# WCHA_SCH.net
KiCad netlist of a schematic drawn in Altium Designer
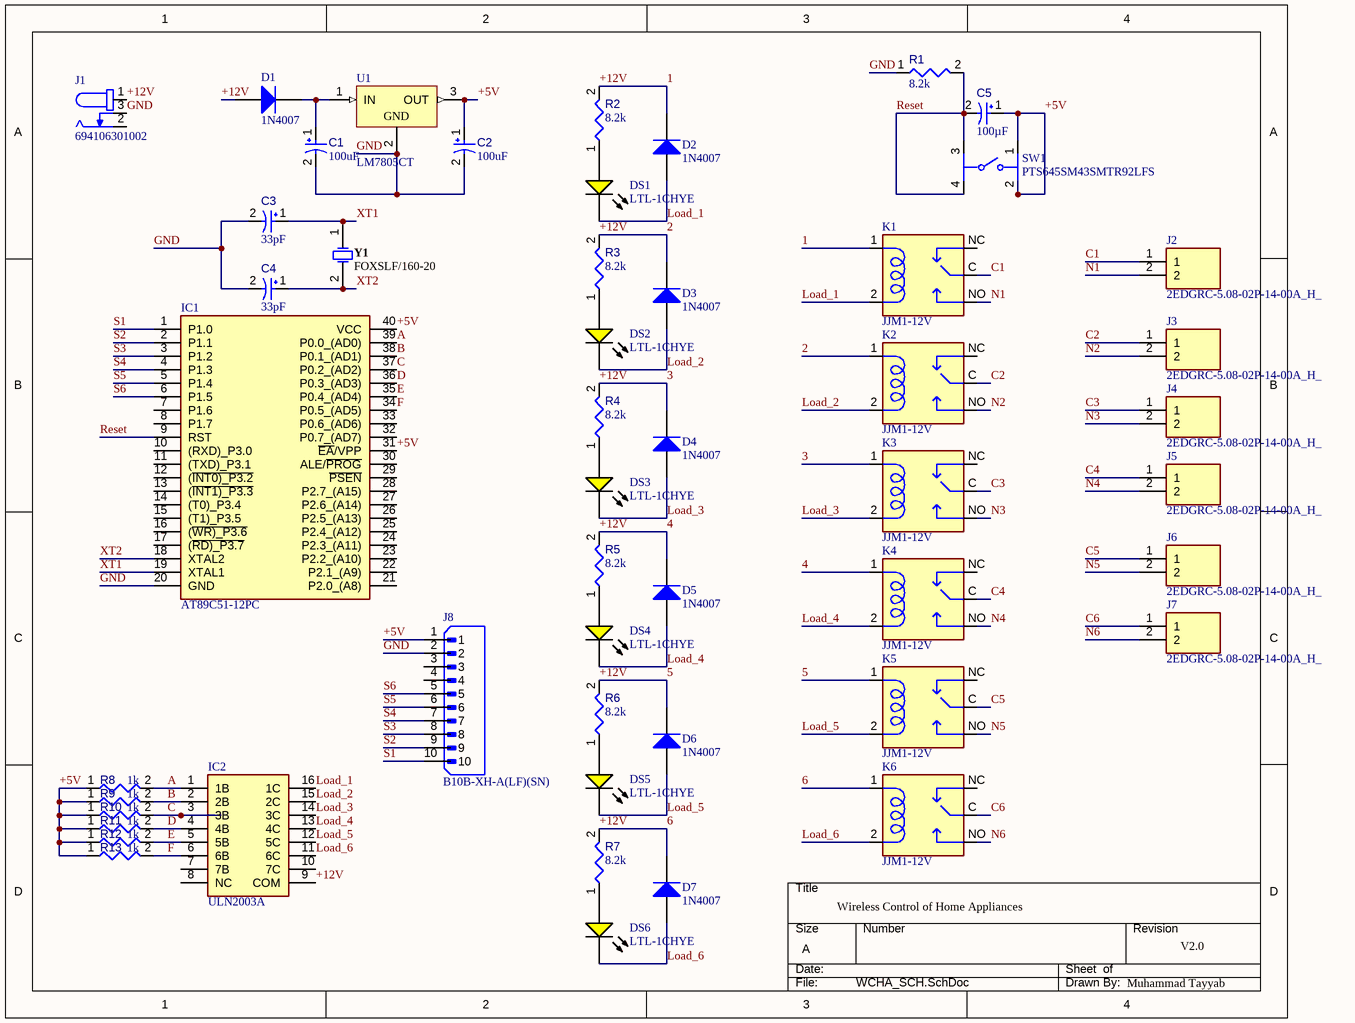
[diagram p0: WCHA_SCH.SchDoc]

(export (version "E")
  (design (tool "Eeschema 10.0.6"))
  (components
    (comp (ref "C1")
      (value "100uF")
      (footprint "CAPPR65-500-2000X1000X2200")
      (description "Aluminum Electrolytic Capacitor, 1000 uF, +/- 20%, 25 V, -40 to 85 degC, 2-Pin THD, RoHS, Bulk")
      (fields (field (name "TOLERANCE") "20%") (field (name "MANUFACTURER") "Panasonic"))
      (libsource (lib "Muhammad Tayyab") (part "CAP-P-2"))
    )
    (comp (ref "C2")
      (value "100uF")
      (footprint "CAPPR65-500-2000X1000X2200")
      (description "Aluminum Electrolytic Capacitor, 1000 uF, +/- 20%, 25 V, -40 to 85 degC, 2-Pin THD, RoHS, Bulk")
      (fields (field (name "TOLERANCE") "20%") (field (name "MANUFACTURER") "Panasonic"))
      (libsource (lib "Muhammad Tayyab") (part "CAP-P-2"))
    )
    (comp (ref "C3")
      (value "33pF")
      (footprint "CAPPR65-350-1150X800X1250")
      (description "Aluminum Electrolytic Capacitor, 100 uF, +/- 20%, 50 V, -40 to 85 degC, 2-Pin THD, RoHS, Bulk")
      (fields (field (name "MANUFACTURER") "Panasonic") (field (name "TOLERANCE") "20%"))
      (libsource (lib "") (part "CAP-P-2_1"))
    )
    (comp (ref "C4")
      (value "33pF")
      (footprint "CAPPR65-350-1150X800X1250")
      (description "Aluminum Electrolytic Capacitor, 100 uF, +/- 20%, 50 V, -40 to 85 degC, 2-Pin THD, RoHS, Bulk")
      (fields (field (name "MANUFACTURER") "Panasonic") (field (name "TOLERANCE") "20%"))
      (libsource (lib "") (part "CAP-P-2_1"))
    )
    (comp (ref "C5")
      (value "100µF")
      (footprint "CAPPR65-350-1150X800X1250")
      (description "Aluminum Electrolytic Capacitor, 100 uF, +/- 20%, 50 V, -40 to 85 degC, 2-Pin THD, RoHS, Bulk")
      (fields (field (name "MANUFACTURER") "Panasonic") (field (name "TOLERANCE") "20%"))
      (libsource (lib "") (part "CAP-P-2_1"))
    )
    (comp (ref "D1")
      (value "1N4007")
      (footprint "FAIR-DO-41-2")
      (description "General Purpose Rectifier, 1.1 V, 1.0 A, -55 to 175 degC, 2-Pin DO-41, RoHS, Tape and Reel")
      (fields (field (name "MANUFACTURER") "Fairchild"))
      (libsource (lib "Muhammad Tayyab") (part "KESE-D_K1A2-2"))
    )
    (comp (ref "D2")
      (value "1N4007")
      (footprint "FAIR-DO-41-2")
      (description "General Purpose Rectifier, 1.1 V, 1.0 A, -55 to 175 degC, 2-Pin DO-41, RoHS, Tape and Reel")
      (fields (field (name "MANUFACTURER") "Fairchild"))
      (libsource (lib "Muhammad Tayyab") (part "KESE-D_K1A2-2"))
    )
    (comp (ref "D3")
      (value "1N4007")
      (footprint "FAIR-DO-41-2")
      (description "General Purpose Rectifier, 1.1 V, 1.0 A, -55 to 175 degC, 2-Pin DO-41, RoHS, Tape and Reel")
      (fields (field (name "MANUFACTURER") "Fairchild"))
      (libsource (lib "Muhammad Tayyab") (part "KESE-D_K1A2-2"))
    )
    (comp (ref "D4")
      (value "1N4007")
      (footprint "FAIR-DO-41-2")
      (description "General Purpose Rectifier, 1.1 V, 1.0 A, -55 to 175 degC, 2-Pin DO-41, RoHS, Tape and Reel")
      (fields (field (name "MANUFACTURER") "Fairchild"))
      (libsource (lib "Muhammad Tayyab") (part "KESE-D_K1A2-2"))
    )
    (comp (ref "D5")
      (value "1N4007")
      (footprint "FAIR-DO-41-2")
      (description "General Purpose Rectifier, 1.1 V, 1.0 A, -55 to 175 degC, 2-Pin DO-41, RoHS, Tape and Reel")
      (fields (field (name "MANUFACTURER") "Fairchild"))
      (libsource (lib "Muhammad Tayyab") (part "KESE-D_K1A2-2"))
    )
    (comp (ref "D6")
      (value "1N4007")
      (footprint "FAIR-DO-41-2")
      (description "General Purpose Rectifier, 1.1 V, 1.0 A, -55 to 175 degC, 2-Pin DO-41, RoHS, Tape and Reel")
      (fields (field (name "MANUFACTURER") "Fairchild"))
      (libsource (lib "Muhammad Tayyab") (part "KESE-D_K1A2-2"))
    )
    (comp (ref "D7")
      (value "1N4007")
      (footprint "FAIR-DO-41-2")
      (description "General Purpose Rectifier, 1.1 V, 1.0 A, -55 to 175 degC, 2-Pin DO-41, RoHS, Tape and Reel")
      (fields (field (name "MANUFACTURER") "Fairchild"))
      (libsource (lib "Muhammad Tayyab") (part "KESE-D_K1A2-2"))
    )
    (comp (ref "DS1")
      (value "LTL-1CHYE")
      (footprint "LTST-LTL-1CHYE")
      (description "LED Uni-Color Yellow, 60 mW, 20 mA, -55 to 100 degC, 2-Pin THD, RoHS, Bulk")
      (fields (field (name "MANUFACTURER") "Lite-On"))
      (libsource (lib "Muhammad Tayyab") (part "LED-YELLOW-AK-2"))
    )
    (comp (ref "DS2")
      (value "LTL-1CHYE")
      (footprint "LTST-LTL-1CHYE")
      (description "LED Uni-Color Yellow, 60 mW, 20 mA, -55 to 100 degC, 2-Pin THD, RoHS, Bulk")
      (fields (field (name "MANUFACTURER") "Lite-On"))
      (libsource (lib "Muhammad Tayyab") (part "LED-YELLOW-AK-2"))
    )
    (comp (ref "DS3")
      (value "LTL-1CHYE")
      (footprint "LTST-LTL-1CHYE")
      (description "LED Uni-Color Yellow, 60 mW, 20 mA, -55 to 100 degC, 2-Pin THD, RoHS, Bulk")
      (fields (field (name "MANUFACTURER") "Lite-On"))
      (libsource (lib "Muhammad Tayyab") (part "LED-YELLOW-AK-2"))
    )
    (comp (ref "DS4")
      (value "LTL-1CHYE")
      (footprint "LTST-LTL-1CHYE")
      (description "LED Uni-Color Yellow, 60 mW, 20 mA, -55 to 100 degC, 2-Pin THD, RoHS, Bulk")
      (fields (field (name "MANUFACTURER") "Lite-On"))
      (libsource (lib "Muhammad Tayyab") (part "LED-YELLOW-AK-2"))
    )
    (comp (ref "DS5")
      (value "LTL-1CHYE")
      (footprint "LTST-LTL-1CHYE")
      (description "LED Uni-Color Yellow, 60 mW, 20 mA, -55 to 100 degC, 2-Pin THD, RoHS, Bulk")
      (fields (field (name "MANUFACTURER") "Lite-On"))
      (libsource (lib "Muhammad Tayyab") (part "LED-YELLOW-AK-2"))
    )
    (comp (ref "DS6")
      (value "LTL-1CHYE")
      (footprint "LTST-LTL-1CHYE")
      (description "LED Uni-Color Yellow, 60 mW, 20 mA, -55 to 100 degC, 2-Pin THD, RoHS, Bulk")
      (fields (field (name "MANUFACTURER") "Lite-On"))
      (libsource (lib "Muhammad Tayyab") (part "LED-YELLOW-AK-2"))
    )
    (comp (ref "IC1")
      (value "AT89C51-12PC")
      (footprint "SamacSys:DIP1525W56P254L5220H559Q40N")
      (description "Integrated Circuit")
      (fields (field (name "MOUSER PART NUMBER") "556-AT89C51-12PC"))
      (libsource (lib "*") (part "AT89C51-12PC"))
    )
    (comp (ref "IC2")
      (value "ULN2003A")
      (footprint "SamacSys:DIP762W54P254L1918H445Q16N")
      (description "Integrated Circuit")
      (libsource (lib "*") (part "ULN2003A"))
    )
    (comp (ref "J1")
      (value "694106301002")
      (footprint "694106301002:694106301002")
      (fields (field (name "MF") "{'manufacturer': u'Wurth Elektronik'}"))
      (libsource (lib "*") (part "694106301002"))
    )
    (comp (ref "J2")
      (value "2EDGRC-5.08-02P-14-00A_H_")
      (footprint "SHDRRA2W100P0X508_1X2_1156X1210X780P")
      (description "R/A SHrouded Header")
      (fields (field (name "MANUFACTURER_PART_NUMBER") "2EDGRC-5.08-02P-14-00A(H)"))
      (libsource (lib "Muhammad Tayyab") (part "2EDGRC-5.08-02P-14-00A_H_"))
    )
    (comp (ref "J3")
      (value "2EDGRC-5.08-02P-14-00A_H_")
      (footprint "SHDRRA2W100P0X508_1X2_1156X1210X780P")
      (description "R/A SHrouded Header")
      (fields (field (name "MANUFACTURER_PART_NUMBER") "2EDGRC-5.08-02P-14-00A(H)"))
      (libsource (lib "Muhammad Tayyab") (part "2EDGRC-5.08-02P-14-00A_H_"))
    )
    (comp (ref "J4")
      (value "2EDGRC-5.08-02P-14-00A_H_")
      (footprint "SHDRRA2W100P0X508_1X2_1156X1210X780P")
      (description "R/A SHrouded Header")
      (fields (field (name "MANUFACTURER_PART_NUMBER") "2EDGRC-5.08-02P-14-00A(H)"))
      (libsource (lib "Muhammad Tayyab") (part "2EDGRC-5.08-02P-14-00A_H_"))
    )
    (comp (ref "J5")
      (value "2EDGRC-5.08-02P-14-00A_H_")
      (footprint "SHDRRA2W100P0X508_1X2_1156X1210X780P")
      (description "R/A SHrouded Header")
      (fields (field (name "MANUFACTURER_PART_NUMBER") "2EDGRC-5.08-02P-14-00A(H)"))
      (libsource (lib "Muhammad Tayyab") (part "2EDGRC-5.08-02P-14-00A_H_"))
    )
    (comp (ref "J6")
      (value "2EDGRC-5.08-02P-14-00A_H_")
      (footprint "SHDRRA2W100P0X508_1X2_1156X1210X780P")
      (description "R/A SHrouded Header")
      (fields (field (name "MANUFACTURER_PART_NUMBER") "2EDGRC-5.08-02P-14-00A(H)"))
      (libsource (lib "Muhammad Tayyab") (part "2EDGRC-5.08-02P-14-00A_H_"))
    )
    (comp (ref "J7")
      (value "2EDGRC-5.08-02P-14-00A_H_")
      (footprint "SHDRRA2W100P0X508_1X2_1156X1210X780P")
      (description "R/A SHrouded Header")
      (fields (field (name "MANUFACTURER_PART_NUMBER") "2EDGRC-5.08-02P-14-00A(H)"))
      (libsource (lib "Muhammad Tayyab") (part "2EDGRC-5.08-02P-14-00A_H_"))
    )
    (comp (ref "J8")
      (value "B10B-XH-A(LF)(SN)")
      (footprint "B10B-XH-A(LF)(SN):JST_B10B-XH-A(LF)(SN)")
      (fields (field (name "MF") "{'manufacturer': u'JST Sales'}"))
      (libsource (lib "*") (part "B10B-XH-A(LF)(SN)"))
    )
    (comp (ref "K1")
      (value "JJM1-12V")
      (footprint "JJM1-12V:RELAY_JJM1-12V")
      (fields (field (name "MF") "{'manufacturer': u'Panasonic Electric'}"))
      (libsource (lib "*") (part "JJM1-12V"))
    )
    (comp (ref "K2")
      (value "JJM1-12V")
      (footprint "JJM1-12V:RELAY_JJM1-12V")
      (fields (field (name "MF") "{'manufacturer': u'Panasonic Electric'}"))
      (libsource (lib "*") (part "JJM1-12V"))
    )
    (comp (ref "K3")
      (value "JJM1-12V")
      (footprint "JJM1-12V:RELAY_JJM1-12V")
      (fields (field (name "MF") "{'manufacturer': u'Panasonic Electric'}"))
      (libsource (lib "*") (part "JJM1-12V"))
    )
    (comp (ref "K4")
      (value "JJM1-12V")
      (footprint "JJM1-12V:RELAY_JJM1-12V")
      (fields (field (name "MF") "{'manufacturer': u'Panasonic Electric'}"))
      (libsource (lib "*") (part "JJM1-12V"))
    )
    (comp (ref "K5")
      (value "JJM1-12V")
      (footprint "JJM1-12V:RELAY_JJM1-12V")
      (fields (field (name "MF") "{'manufacturer': u'Panasonic Electric'}"))
      (libsource (lib "*") (part "JJM1-12V"))
    )
    (comp (ref "K6")
      (value "JJM1-12V")
      (footprint "JJM1-12V:RELAY_JJM1-12V")
      (fields (field (name "MF") "{'manufacturer': u'Panasonic Electric'}"))
      (libsource (lib "*") (part "JJM1-12V"))
    )
    (comp (ref "R1")
      (value "8.2k")
      (footprint "RESA60-630X240")
      (description "Axial Resistor, 47.5 KOhm, +/- 1%, 0.25 W, -55 to 155 degC, 2-Pin THD, RoHS, Bulk")
      (fields (field (name "MANUFACTURER") "Yageo") (field (name "TOLERANCE") "1%"))
      (libsource (lib "Muhammad Tayyab") (part "RES-2"))
    )
    (comp (ref "R2")
      (value "8.2k")
      (footprint "RESA60-630X240")
      (description "Axial Resistor, 47.5 KOhm, +/- 1%, 0.25 W, -55 to 155 degC, 2-Pin THD, RoHS, Bulk")
      (fields (field (name "MANUFACTURER") "Yageo") (field (name "TOLERANCE") "1%"))
      (libsource (lib "Muhammad Tayyab") (part "RES-2"))
    )
    (comp (ref "R3")
      (value "8.2k")
      (footprint "RESA60-630X240")
      (description "Axial Resistor, 47.5 KOhm, +/- 1%, 0.25 W, -55 to 155 degC, 2-Pin THD, RoHS, Bulk")
      (fields (field (name "MANUFACTURER") "Yageo") (field (name "TOLERANCE") "1%"))
      (libsource (lib "Muhammad Tayyab") (part "RES-2"))
    )
    (comp (ref "R4")
      (value "8.2k")
      (footprint "RESA60-630X240")
      (description "Axial Resistor, 47.5 KOhm, +/- 1%, 0.25 W, -55 to 155 degC, 2-Pin THD, RoHS, Bulk")
      (fields (field (name "MANUFACTURER") "Yageo") (field (name "TOLERANCE") "1%"))
      (libsource (lib "Muhammad Tayyab") (part "RES-2"))
    )
    (comp (ref "R5")
      (value "8.2k")
      (footprint "RESA60-630X240")
      (description "Axial Resistor, 47.5 KOhm, +/- 1%, 0.25 W, -55 to 155 degC, 2-Pin THD, RoHS, Bulk")
      (fields (field (name "MANUFACTURER") "Yageo") (field (name "TOLERANCE") "1%"))
      (libsource (lib "Muhammad Tayyab") (part "RES-2"))
    )
    (comp (ref "R6")
      (value "8.2k")
      (footprint "RESA60-630X240")
      (description "Axial Resistor, 47.5 KOhm, +/- 1%, 0.25 W, -55 to 155 degC, 2-Pin THD, RoHS, Bulk")
      (fields (field (name "MANUFACTURER") "Yageo") (field (name "TOLERANCE") "1%"))
      (libsource (lib "Muhammad Tayyab") (part "RES-2"))
    )
    (comp (ref "R7")
      (value "8.2k")
      (footprint "RESA60-630X240")
      (description "Axial Resistor, 47.5 KOhm, +/- 1%, 0.25 W, -55 to 155 degC, 2-Pin THD, RoHS, Bulk")
      (fields (field (name "MANUFACTURER") "Yageo") (field (name "TOLERANCE") "1%"))
      (libsource (lib "Muhammad Tayyab") (part "RES-2"))
    )
    (comp (ref "R8")
      (value "1k")
      (footprint "RESA60-630X240")
      (description "Axial Resistor, 47.5 KOhm, +/- 1%, 0.25 W, -55 to 155 degC, 2-Pin THD, RoHS, Bulk")
      (fields (field (name "MANUFACTURER") "Yageo") (field (name "TOLERANCE") "1%"))
      (libsource (lib "Muhammad Tayyab") (part "RES-2"))
    )
    (comp (ref "R9")
      (value "1k")
      (footprint "RESA60-630X240")
      (description "Axial Resistor, 47.5 KOhm, +/- 1%, 0.25 W, -55 to 155 degC, 2-Pin THD, RoHS, Bulk")
      (fields (field (name "MANUFACTURER") "Yageo") (field (name "TOLERANCE") "1%"))
      (libsource (lib "Muhammad Tayyab") (part "RES-2"))
    )
    (comp (ref "R10")
      (value "1k")
      (footprint "RESA60-630X240")
      (description "Axial Resistor, 47.5 KOhm, +/- 1%, 0.25 W, -55 to 155 degC, 2-Pin THD, RoHS, Bulk")
      (fields (field (name "MANUFACTURER") "Yageo") (field (name "TOLERANCE") "1%"))
      (libsource (lib "Muhammad Tayyab") (part "RES-2"))
    )
    (comp (ref "R11")
      (value "1k")
      (footprint "RESA60-630X240")
      (description "Axial Resistor, 47.5 KOhm, +/- 1%, 0.25 W, -55 to 155 degC, 2-Pin THD, RoHS, Bulk")
      (fields (field (name "MANUFACTURER") "Yageo") (field (name "TOLERANCE") "1%"))
      (libsource (lib "Muhammad Tayyab") (part "RES-2"))
    )
    (comp (ref "R12")
      (value "1k")
      (footprint "RESA60-630X240")
      (description "Axial Resistor, 47.5 KOhm, +/- 1%, 0.25 W, -55 to 155 degC, 2-Pin THD, RoHS, Bulk")
      (fields (field (name "MANUFACTURER") "Yageo") (field (name "TOLERANCE") "1%"))
      (libsource (lib "Muhammad Tayyab") (part "RES-2"))
    )
    (comp (ref "R13")
      (value "1k")
      (footprint "RESA60-630X240")
      (description "Axial Resistor, 47.5 KOhm, +/- 1%, 0.25 W, -55 to 155 degC, 2-Pin THD, RoHS, Bulk")
      (fields (field (name "MANUFACTURER") "Yageo") (field (name "TOLERANCE") "1%"))
      (libsource (lib "Muhammad Tayyab") (part "RES-2"))
    )
    (comp (ref "SW1")
      (value "PTS645SM43SMTR92LFS")
      (footprint "FP-PTS645SM43SMTR92LFS-MFG")
      (description "SWITCH TACTILE SPST-NO 0.05A 12V")
      (libsource (lib "Altium Content Vault") (part "1adf0dd01260c80cf25a44bfd6b99ba"))
    )
    (comp (ref "U1")
      (value "LM7805CT")
      (footprint "FAIR-TO-220-3")
      (description "Positive Voltage Regulator, 5 V, 1 A, -40 to 125 degC, 3-Pin TO-220, RoHS, Tube")
      (fields (field (name "MANUFACTURER") "FairchildSemiconductor"))
      (libsource (lib "Altium Content Vault") (part "FAIR-LM7805CT-TO220-3"))
    )
    (comp (ref "Y1")
      (value "FOXSLF/160-20")
      (footprint "FOX-FOXSLF160-20")
      (fields (field (name "MANUFACTURER") "FOX Electronics") (field (name "TOLERANCE") "50ppm"))
      (libsource (lib "Muhammad Tayyab") (part "XTAL-1-2-2"))
    )
  )
  (nets
    (net (code "1") (name "/+5V") (class "Default")
      (node (ref "C2") (pin "1") (pinfunction "1_1") (pintype "passive"))
      (node (ref "C5") (pin "1") (pinfunction "1_1") (pintype "passive"))
      (node (ref "IC1") (pin "31") (pinfunction "~{EA}/VPP_31") (pintype "passive"))
      (node (ref "IC1") (pin "40") (pinfunction "VCC_40") (pintype "passive"))
      (node (ref "J8") (pin "1") (pinfunction "1_1") (pintype "passive"))
      (node (ref "R10") (pin "1") (pinfunction "1_1") (pintype "passive"))
      (node (ref "R11") (pin "1") (pinfunction "1_1") (pintype "passive"))
      (node (ref "R12") (pin "1") (pinfunction "1_1") (pintype "passive"))
      (node (ref "R13") (pin "1") (pinfunction "1_1") (pintype "passive"))
      (node (ref "R8") (pin "1") (pinfunction "1_1") (pintype "passive"))
      (node (ref "R9") (pin "1") (pinfunction "1_1") (pintype "passive"))
      (node (ref "SW1") (pin "1") (pinfunction "1_1") (pintype "passive"))
      (node (ref "SW1") (pin "2") (pinfunction "2_2") (pintype "passive"))
      (node (ref "U1") (pin "3") (pinfunction "OUT_3") (pintype "output"))
    )
    (net (code "2") (name "/+12V") (class "Default")
      (node (ref "D1") (pin "2") (pinfunction "A_2") (pintype "passive"))
      (node (ref "D2") (pin "1") (pinfunction "K_1") (pintype "passive"))
      (node (ref "D3") (pin "1") (pinfunction "K_1") (pintype "passive"))
      (node (ref "D4") (pin "1") (pinfunction "K_1") (pintype "passive"))
      (node (ref "D5") (pin "1") (pinfunction "K_1") (pintype "passive"))
      (node (ref "D6") (pin "1") (pinfunction "K_1") (pintype "passive"))
      (node (ref "D7") (pin "1") (pinfunction "K_1") (pintype "passive"))
      (node (ref "IC2") (pin "9") (pinfunction "COM_9") (pintype "passive"))
      (node (ref "J1") (pin "1") (pinfunction "1_1") (pintype "passive"))
      (node (ref "K1") (pin "1") (pinfunction "C1_1") (pintype "passive"))
      (node (ref "K2") (pin "1") (pinfunction "C1_1") (pintype "passive"))
      (node (ref "K3") (pin "1") (pinfunction "C1_1") (pintype "passive"))
      (node (ref "K4") (pin "1") (pinfunction "C1_1") (pintype "passive"))
      (node (ref "K5") (pin "1") (pinfunction "C1_1") (pintype "passive"))
      (node (ref "K6") (pin "1") (pinfunction "C1_1") (pintype "passive"))
      (node (ref "R2") (pin "2") (pinfunction "2_2") (pintype "passive"))
      (node (ref "R3") (pin "2") (pinfunction "2_2") (pintype "passive"))
      (node (ref "R4") (pin "2") (pinfunction "2_2") (pintype "passive"))
      (node (ref "R5") (pin "2") (pinfunction "2_2") (pintype "passive"))
      (node (ref "R6") (pin "2") (pinfunction "2_2") (pintype "passive"))
      (node (ref "R7") (pin "2") (pinfunction "2_2") (pintype "passive"))
    )
    (net (code "4") (name "/A") (class "Default")
      (node (ref "IC1") (pin "39") (pinfunction "P0.0_(AD0)_39") (pintype "passive"))
      (node (ref "IC2") (pin "1") (pinfunction "1B_1") (pintype "passive"))
      (node (ref "R8") (pin "2") (pinfunction "2_2") (pintype "passive"))
    )
    (net (code "5") (name "/B") (class "Default")
      (node (ref "IC1") (pin "38") (pinfunction "P0.1_(AD1)_38") (pintype "passive"))
      (node (ref "IC2") (pin "2") (pinfunction "2B_2") (pintype "passive"))
      (node (ref "R9") (pin "2") (pinfunction "2_2") (pintype "passive"))
    )
    (net (code "6") (name "/C") (class "Default")
      (node (ref "IC1") (pin "37") (pinfunction "P0.2_(AD2)_37") (pintype "passive"))
      (node (ref "IC2") (pin "3") (pinfunction "3B_3") (pintype "passive"))
      (node (ref "R10") (pin "2") (pinfunction "2_2") (pintype "passive"))
    )
    (net (code "7") (name "/C1") (class "Default")
      (node (ref "J2") (pin "1") (pinfunction "1_1") (pintype "passive"))
      (node (ref "K1") (pin "C") (pinfunction "M_C") (pintype "passive"))
    )
    (net (code "8") (name "/C2") (class "Default")
      (node (ref "J3") (pin "1") (pinfunction "1_1") (pintype "passive"))
      (node (ref "K2") (pin "C") (pinfunction "M_C") (pintype "passive"))
    )
    (net (code "9") (name "/C3") (class "Default")
      (node (ref "J4") (pin "1") (pinfunction "1_1") (pintype "passive"))
      (node (ref "K3") (pin "C") (pinfunction "M_C") (pintype "passive"))
    )
    (net (code "10") (name "/C4") (class "Default")
      (node (ref "J5") (pin "1") (pinfunction "1_1") (pintype "passive"))
      (node (ref "K4") (pin "C") (pinfunction "M_C") (pintype "passive"))
    )
    (net (code "11") (name "/C5") (class "Default")
      (node (ref "J6") (pin "1") (pinfunction "1_1") (pintype "passive"))
      (node (ref "K5") (pin "C") (pinfunction "M_C") (pintype "passive"))
    )
    (net (code "12") (name "/C6") (class "Default")
      (node (ref "J7") (pin "1") (pinfunction "1_1") (pintype "passive"))
      (node (ref "K6") (pin "C") (pinfunction "M_C") (pintype "passive"))
    )
    (net (code "13") (name "/D") (class "Default")
      (node (ref "IC1") (pin "36") (pinfunction "P0.3_(AD3)_36") (pintype "passive"))
      (node (ref "IC2") (pin "4") (pinfunction "4B_4") (pintype "passive"))
      (node (ref "R11") (pin "2") (pinfunction "2_2") (pintype "passive"))
    )
    (net (code "14") (name "/E") (class "Default")
      (node (ref "IC1") (pin "35") (pinfunction "P0.4_(AD4)_35") (pintype "passive"))
      (node (ref "IC2") (pin "5") (pinfunction "5B_5") (pintype "passive"))
      (node (ref "R12") (pin "2") (pinfunction "2_2") (pintype "passive"))
    )
    (net (code "15") (name "/F") (class "Default")
      (node (ref "IC1") (pin "34") (pinfunction "P0.5_(AD5)_34") (pintype "passive"))
      (node (ref "IC2") (pin "6") (pinfunction "6B_6") (pintype "passive"))
      (node (ref "R13") (pin "2") (pinfunction "2_2") (pintype "passive"))
    )
    (net (code "16") (name "/GND") (class "Default")
      (node (ref "C1") (pin "2") (pinfunction "2_2") (pintype "passive"))
      (node (ref "C2") (pin "2") (pinfunction "2_2") (pintype "passive"))
      (node (ref "C3") (pin "2") (pinfunction "2_2") (pintype "passive"))
      (node (ref "C4") (pin "2") (pinfunction "2_2") (pintype "passive"))
      (node (ref "IC1") (pin "20") (pinfunction "GND_20") (pintype "passive"))
      (node (ref "J1") (pin "3") (pinfunction "3_3") (pintype "passive"))
      (node (ref "J8") (pin "2") (pinfunction "2_2") (pintype "passive"))
      (node (ref "R1") (pin "1") (pinfunction "1_1") (pintype "passive"))
      (node (ref "U1") (pin "2") (pinfunction "GND_2") (pintype "power_in"))
    )
    (net (code "17") (name "/Load_1") (class "Default")
      (node (ref "D2") (pin "2") (pinfunction "A_2") (pintype "passive"))
      (node (ref "DS1") (pin "2") (pinfunction "K_2") (pintype "passive"))
      (node (ref "IC2") (pin "16") (pinfunction "1C_16") (pintype "passive"))
      (node (ref "K1") (pin "2") (pinfunction "C2_2") (pintype "passive"))
    )
    (net (code "18") (name "/Load_2") (class "Default")
      (node (ref "D3") (pin "2") (pinfunction "A_2") (pintype "passive"))
      (node (ref "DS2") (pin "2") (pinfunction "K_2") (pintype "passive"))
      (node (ref "IC2") (pin "15") (pinfunction "2C_15") (pintype "passive"))
      (node (ref "K2") (pin "2") (pinfunction "C2_2") (pintype "passive"))
    )
    (net (code "19") (name "/Load_3") (class "Default")
      (node (ref "D4") (pin "2") (pinfunction "A_2") (pintype "passive"))
      (node (ref "DS3") (pin "2") (pinfunction "K_2") (pintype "passive"))
      (node (ref "IC2") (pin "14") (pinfunction "3C_14") (pintype "passive"))
      (node (ref "K3") (pin "2") (pinfunction "C2_2") (pintype "passive"))
    )
    (net (code "20") (name "/Load_4") (class "Default")
      (node (ref "D5") (pin "2") (pinfunction "A_2") (pintype "passive"))
      (node (ref "DS4") (pin "2") (pinfunction "K_2") (pintype "passive"))
      (node (ref "IC2") (pin "13") (pinfunction "4C_13") (pintype "passive"))
      (node (ref "K4") (pin "2") (pinfunction "C2_2") (pintype "passive"))
    )
    (net (code "21") (name "/Load_5") (class "Default")
      (node (ref "D6") (pin "2") (pinfunction "A_2") (pintype "passive"))
      (node (ref "DS5") (pin "2") (pinfunction "K_2") (pintype "passive"))
      (node (ref "IC2") (pin "12") (pinfunction "5C_12") (pintype "passive"))
      (node (ref "K5") (pin "2") (pinfunction "C2_2") (pintype "passive"))
    )
    (net (code "22") (name "/Load_6") (class "Default")
      (node (ref "D7") (pin "2") (pinfunction "A_2") (pintype "passive"))
      (node (ref "DS6") (pin "2") (pinfunction "K_2") (pintype "passive"))
      (node (ref "IC2") (pin "11") (pinfunction "6C_11") (pintype "passive"))
      (node (ref "K6") (pin "2") (pinfunction "C2_2") (pintype "passive"))
    )
    (net (code "23") (name "/N1") (class "Default")
      (node (ref "J2") (pin "2") (pinfunction "2_2") (pintype "passive"))
      (node (ref "K1") (pin "NO") (pinfunction "NO_NO") (pintype "passive"))
    )
    (net (code "24") (name "/N2") (class "Default")
      (node (ref "J3") (pin "2") (pinfunction "2_2") (pintype "passive"))
      (node (ref "K2") (pin "NO") (pinfunction "NO_NO") (pintype "passive"))
    )
    (net (code "25") (name "/N3") (class "Default")
      (node (ref "J4") (pin "2") (pinfunction "2_2") (pintype "passive"))
      (node (ref "K3") (pin "NO") (pinfunction "NO_NO") (pintype "passive"))
    )
    (net (code "26") (name "/N4") (class "Default")
      (node (ref "J5") (pin "2") (pinfunction "2_2") (pintype "passive"))
      (node (ref "K4") (pin "NO") (pinfunction "NO_NO") (pintype "passive"))
    )
    (net (code "27") (name "/N5") (class "Default")
      (node (ref "J6") (pin "2") (pinfunction "2_2") (pintype "passive"))
      (node (ref "K5") (pin "NO") (pinfunction "NO_NO") (pintype "passive"))
    )
    (net (code "28") (name "/N6") (class "Default")
      (node (ref "J7") (pin "2") (pinfunction "2_2") (pintype "passive"))
      (node (ref "K6") (pin "NO") (pinfunction "NO_NO") (pintype "passive"))
    )
    (net (code "29") (name "/Reset") (class "Default")
      (node (ref "C5") (pin "2") (pinfunction "2_2") (pintype "passive"))
      (node (ref "IC1") (pin "9") (pinfunction "RST_9") (pintype "passive"))
      (node (ref "R1") (pin "2") (pinfunction "2_2") (pintype "passive"))
      (node (ref "SW1") (pin "3") (pinfunction "3_3") (pintype "passive"))
      (node (ref "SW1") (pin "4") (pinfunction "4_4") (pintype "passive"))
    )
    (net (code "30") (name "/S1") (class "Default")
      (node (ref "IC1") (pin "1") (pinfunction "P1.0_1") (pintype "passive"))
      (node (ref "J8") (pin "10") (pinfunction "10_10") (pintype "passive"))
    )
    (net (code "31") (name "/S2") (class "Default")
      (node (ref "IC1") (pin "2") (pinfunction "P1.1_2") (pintype "passive"))
      (node (ref "J8") (pin "9") (pinfunction "9_9") (pintype "passive"))
    )
    (net (code "32") (name "/S3") (class "Default")
      (node (ref "IC1") (pin "3") (pinfunction "P1.2_3") (pintype "passive"))
      (node (ref "J8") (pin "8") (pinfunction "8_8") (pintype "passive"))
    )
    (net (code "33") (name "/S4") (class "Default")
      (node (ref "IC1") (pin "4") (pinfunction "P1.3_4") (pintype "passive"))
      (node (ref "J8") (pin "7") (pinfunction "7_7") (pintype "passive"))
    )
    (net (code "34") (name "/S5") (class "Default")
      (node (ref "IC1") (pin "5") (pinfunction "P1.4_5") (pintype "passive"))
      (node (ref "J8") (pin "6") (pinfunction "6_6") (pintype "passive"))
    )
    (net (code "35") (name "/S6") (class "Default")
      (node (ref "IC1") (pin "6") (pinfunction "P1.5_6") (pintype "passive"))
      (node (ref "J8") (pin "5") (pinfunction "5_5") (pintype "passive"))
    )
    (net (code "36") (name "/XT1") (class "Default")
      (node (ref "C3") (pin "1") (pinfunction "1_1") (pintype "passive"))
      (node (ref "IC1") (pin "19") (pinfunction "XTAL1_19") (pintype "passive"))
      (node (ref "Y1") (pin "1") (pinfunction "1_1") (pintype "passive"))
    )
    (net (code "37") (name "/XT2") (class "Default")
      (node (ref "C4") (pin "1") (pinfunction "1_1") (pintype "passive"))
      (node (ref "IC1") (pin "18") (pinfunction "XTAL2_18") (pintype "passive"))
      (node (ref "Y1") (pin "2") (pinfunction "2_2") (pintype "passive"))
    )
    (net (code "38") (name "Net-(D1-K)") (class "Default")
      (node (ref "C1") (pin "1") (pinfunction "1_1") (pintype "passive"))
      (node (ref "D1") (pin "1") (pinfunction "K_1") (pintype "passive"))
      (node (ref "U1") (pin "1") (pinfunction "IN_1") (pintype "input"))
    )
    (net (code "39") (name "Net-(DS1-A)") (class "Default")
      (node (ref "DS1") (pin "1") (pinfunction "A_1") (pintype "passive"))
      (node (ref "R2") (pin "1") (pinfunction "1_1") (pintype "passive"))
    )
    (net (code "40") (name "Net-(DS2-A)") (class "Default")
      (node (ref "DS2") (pin "1") (pinfunction "A_1") (pintype "passive"))
      (node (ref "R3") (pin "1") (pinfunction "1_1") (pintype "passive"))
    )
    (net (code "41") (name "Net-(DS3-A)") (class "Default")
      (node (ref "DS3") (pin "1") (pinfunction "A_1") (pintype "passive"))
      (node (ref "R4") (pin "1") (pinfunction "1_1") (pintype "passive"))
    )
    (net (code "42") (name "Net-(DS4-A)") (class "Default")
      (node (ref "DS4") (pin "1") (pinfunction "A_1") (pintype "passive"))
      (node (ref "R5") (pin "1") (pinfunction "1_1") (pintype "passive"))
    )
    (net (code "43") (name "Net-(DS5-A)") (class "Default")
      (node (ref "DS5") (pin "1") (pinfunction "A_1") (pintype "passive"))
      (node (ref "R6") (pin "1") (pinfunction "1_1") (pintype "passive"))
    )
    (net (code "44") (name "Net-(DS6-A)") (class "Default")
      (node (ref "DS6") (pin "1") (pinfunction "A_1") (pintype "passive"))
      (node (ref "R7") (pin "1") (pinfunction "1_1") (pintype "passive"))
    )
    (net (code "45") (name "unconnected-(IC1-(RXD)_P3.0-Pad10)") (class "Default")
      (node (ref "IC1") (pin "10") (pinfunction "(RXD)_P3.0_10") (pintype "passive"))
    )
    (net (code "46") (name "unconnected-(IC1-(T0)_P3.4-Pad14)") (class "Default")
      (node (ref "IC1") (pin "14") (pinfunction "(T0)_P3.4_14") (pintype "passive"))
    )
    (net (code "47") (name "unconnected-(IC1-(T1)_P3.5-Pad15)") (class "Default")
      (node (ref "IC1") (pin "15") (pinfunction "(T1)_P3.5_15") (pintype "passive"))
    )
    (net (code "48") (name "unconnected-(IC1-(TXD)_P3.1-Pad11)") (class "Default")
      (node (ref "IC1") (pin "11") (pinfunction "(TXD)_P3.1_11") (pintype "passive"))
    )
    (net (code "49") (name "unconnected-(IC1-(~{INT0)_P3.2}-Pad12)") (class "Default")
      (node (ref "IC1") (pin "12") (pinfunction "(~{INT0)_P3.2}_12") (pintype "passive"))
    )
    (net (code "50") (name "unconnected-(IC1-(~{INT1)_P3.3}-Pad13)") (class "Default")
      (node (ref "IC1") (pin "13") (pinfunction "(~{INT1)_P3.3}_13") (pintype "passive"))
    )
    (net (code "51") (name "unconnected-(IC1-(~{RD)_P3.7}-Pad17)") (class "Default")
      (node (ref "IC1") (pin "17") (pinfunction "(~{RD)_P3.7}_17") (pintype "passive"))
    )
    (net (code "52") (name "unconnected-(IC1-(~{WR)_P3.6}-Pad16)") (class "Default")
      (node (ref "IC1") (pin "16") (pinfunction "(~{WR)_P3.6}_16") (pintype "passive"))
    )
    (net (code "53") (name "unconnected-(IC1-ALE{slash}~{PROG}-Pad30)") (class "Default")
      (node (ref "IC1") (pin "30") (pinfunction "ALE/~{PROG}_30") (pintype "passive"))
    )
    (net (code "54") (name "unconnected-(IC1-P0.6_(AD6)-Pad33)") (class "Default")
      (node (ref "IC1") (pin "33") (pinfunction "P0.6_(AD6)_33") (pintype "passive"))
    )
    (net (code "55") (name "unconnected-(IC1-P0.7_(AD7)-Pad32)") (class "Default")
      (node (ref "IC1") (pin "32") (pinfunction "P0.7_(AD7)_32") (pintype "passive"))
    )
    (net (code "56") (name "unconnected-(IC1-P1.6-Pad7)") (class "Default")
      (node (ref "IC1") (pin "7") (pinfunction "P1.6_7") (pintype "passive"))
    )
    (net (code "57") (name "unconnected-(IC1-P1.7-Pad8)") (class "Default")
      (node (ref "IC1") (pin "8") (pinfunction "P1.7_8") (pintype "passive"))
    )
    (net (code "58") (name "unconnected-(IC1-P2.0_(A8)-Pad21)") (class "Default")
      (node (ref "IC1") (pin "21") (pinfunction "P2.0_(A8)_21") (pintype "passive"))
    )
    (net (code "59") (name "unconnected-(IC1-P2.1_(A9)-Pad22)") (class "Default")
      (node (ref "IC1") (pin "22") (pinfunction "P2.1_(A9)_22") (pintype "passive"))
    )
    (net (code "60") (name "unconnected-(IC1-P2.2_(A10)-Pad23)") (class "Default")
      (node (ref "IC1") (pin "23") (pinfunction "P2.2_(A10)_23") (pintype "passive"))
    )
    (net (code "61") (name "unconnected-(IC1-P2.3_(A11)-Pad24)") (class "Default")
      (node (ref "IC1") (pin "24") (pinfunction "P2.3_(A11)_24") (pintype "passive"))
    )
    (net (code "62") (name "unconnected-(IC1-P2.4_(A12)-Pad25)") (class "Default")
      (node (ref "IC1") (pin "25") (pinfunction "P2.4_(A12)_25") (pintype "passive"))
    )
    (net (code "63") (name "unconnected-(IC1-P2.5_(A13)-Pad26)") (class "Default")
      (node (ref "IC1") (pin "26") (pinfunction "P2.5_(A13)_26") (pintype "passive"))
    )
    (net (code "64") (name "unconnected-(IC1-P2.6_(A14)-Pad27)") (class "Default")
      (node (ref "IC1") (pin "27") (pinfunction "P2.6_(A14)_27") (pintype "passive"))
    )
    (net (code "65") (name "unconnected-(IC1-P2.7_(A15)-Pad28)") (class "Default")
      (node (ref "IC1") (pin "28") (pinfunction "P2.7_(A15)_28") (pintype "passive"))
    )
    (net (code "66") (name "unconnected-(IC1-~{PSEN}-Pad29)") (class "Default")
      (node (ref "IC1") (pin "29") (pinfunction "~{PSEN}_29") (pintype "passive"))
    )
    (net (code "67") (name "unconnected-(IC2-7B-Pad7)") (class "Default")
      (node (ref "IC2") (pin "7") (pinfunction "7B_7") (pintype "passive"))
    )
    (net (code "68") (name "unconnected-(IC2-7C-Pad10)") (class "Default")
      (node (ref "IC2") (pin "10") (pinfunction "7C_10") (pintype "passive"))
    )
    (net (code "69") (name "unconnected-(IC2-NC-Pad8)") (class "Default")
      (node (ref "IC2") (pin "8") (pinfunction "NC_8") (pintype "passive"))
    )
    (net (code "70") (name "unconnected-(J1-Pad2)") (class "Default")
      (node (ref "J1") (pin "2") (pinfunction "2_2") (pintype "passive"))
    )
    (net (code "71") (name "unconnected-(J8-Pad3)") (class "Default")
      (node (ref "J8") (pin "3") (pinfunction "3_3") (pintype "passive"))
    )
    (net (code "72") (name "unconnected-(J8-Pad4)") (class "Default")
      (node (ref "J8") (pin "4") (pinfunction "4_4") (pintype "passive"))
    )
    (net (code "73") (name "unconnected-(K1-PadNC)") (class "Default")
      (node (ref "K1") (pin "NC") (pinfunction "NC_NC") (pintype "passive"))
    )
    (net (code "74") (name "unconnected-(K2-PadNC)") (class "Default")
      (node (ref "K2") (pin "NC") (pinfunction "NC_NC") (pintype "passive"))
    )
    (net (code "75") (name "unconnected-(K3-PadNC)") (class "Default")
      (node (ref "K3") (pin "NC") (pinfunction "NC_NC") (pintype "passive"))
    )
    (net (code "76") (name "unconnected-(K4-PadNC)") (class "Default")
      (node (ref "K4") (pin "NC") (pinfunction "NC_NC") (pintype "passive"))
    )
    (net (code "77") (name "unconnected-(K5-PadNC)") (class "Default")
      (node (ref "K5") (pin "NC") (pinfunction "NC_NC") (pintype "passive"))
    )
    (net (code "78") (name "unconnected-(K6-PadNC)") (class "Default")
      (node (ref "K6") (pin "NC") (pinfunction "NC_NC") (pintype "passive"))
    )
  )
)
